# pcb_clk.net
KiCad netlist of a schematic drawn in Altium Designer
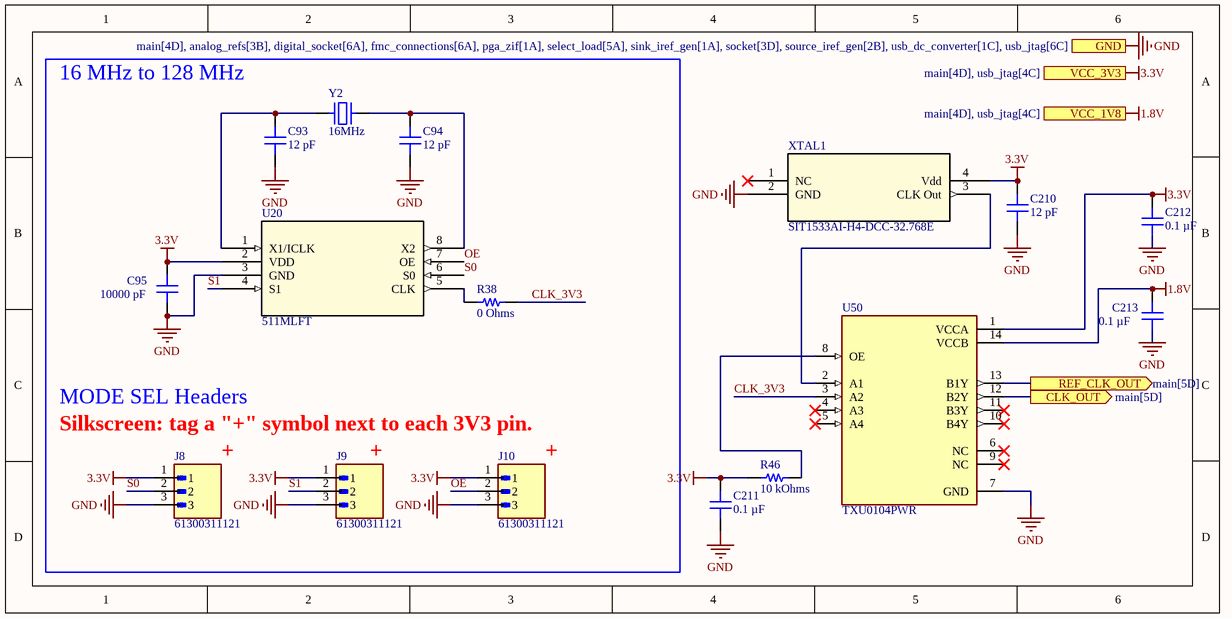
[diagram p0: pcb_clk.SchDoc]

(export (version "E")
  (design (tool "Eeschema 10.0.6"))
  (components
    (comp (ref "C93")
      (value "12 pF")
      (footprint "CAP 0805_2012")
      (description "CAP CER 12PF 250V NP0 0805")
      (fields
        (field (name "PART NUMBER") "251R15S120GV4E")
        (field (name "CAPACITANCE") "12 pF")
        (field (name "MANUFACTURER") "Johanson Technology Inc.")
      )
      (libsource (lib "Celestial Altium Library - altium_library") (part "Capacitor"))
    )
    (comp (ref "C94")
      (value "12 pF")
      (footprint "CAP 0805_2012")
      (description "CAP CER 12PF 250V NP0 0805")
      (fields
        (field (name "PART NUMBER") "251R15S120GV4E")
        (field (name "CAPACITANCE") "12 pF")
        (field (name "MANUFACTURER") "Johanson Technology Inc.")
      )
      (libsource (lib "Celestial Altium Library - altium_library") (part "Capacitor"))
    )
    (comp (ref "C95")
      (value "10000 pF")
      (footprint "CAP 0805_2012")
      (description "CAP CER 0805 10NF 25V C0G 1%")
      (fields
        (field (name "PART NUMBER") "C0805C103F3GEC7800")
        (field (name "CAPACITANCE") "10000 pF")
        (field (name "MANUFACTURER") "KEMET")
      )
      (libsource (lib "Celestial Altium Library - altium_library") (part "Capacitor"))
    )
    (comp (ref "C210")
      (value "12 pF")
      (footprint "CAP 0805_2012")
      (description "CAP CER 12PF 250V NP0 0805")
      (fields
        (field (name "PART NUMBER") "251R15S120GV4E")
        (field (name "CAPACITANCE") "12 pF")
        (field (name "MANUFACTURER") "Johanson Technology Inc.")
      )
      (libsource (lib "Celestial Altium Library - altium_library") (part "Capacitor"))
    )
    (comp (ref "C211")
      (value "0.1 µF")
      (footprint "CAP 0805_2012")
      (description "CAP CER 0.1UF 16V X7R 0805")
      (fields
        (field (name "PART NUMBER") "160R15W104KV4T")
        (field (name "CAPACITANCE") "0.1 µF")
        (field (name "MANUFACTURER") "Johanson Dielectrics Inc.")
      )
      (libsource (lib "Celestial Altium Library - altium_library") (part "Capacitor"))
    )
    (comp (ref "C212")
      (value "0.1 µF")
      (footprint "CAP 0805_2012")
      (description "CAP CER 0.1UF 16V X7R 0805")
      (fields
        (field (name "PART NUMBER") "160R15W104KV4T")
        (field (name "CAPACITANCE") "0.1 µF")
        (field (name "MANUFACTURER") "Johanson Dielectrics Inc.")
      )
      (libsource (lib "Celestial Altium Library - altium_library") (part "Capacitor"))
    )
    (comp (ref "C213")
      (value "0.1 µF")
      (footprint "CAP 0805_2012")
      (description "CAP CER 0.1UF 16V X7R 0805")
      (fields
        (field (name "PART NUMBER") "160R15W104KV4T")
        (field (name "CAPACITANCE") "0.1 µF")
        (field (name "MANUFACTURER") "Johanson Dielectrics Inc.")
      )
      (libsource (lib "Celestial Altium Library - altium_library") (part "Capacitor"))
    )
    (comp (ref "J8")
      (value "61300311121")
      (footprint "WURTH_61300311121")
      (libsource (lib "Connectors") (part "61300311121"))
    )
    (comp (ref "J9")
      (value "61300311121")
      (footprint "WURTH_61300311121")
      (libsource (lib "Connectors") (part "61300311121"))
    )
    (comp (ref "J10")
      (value "61300311121")
      (footprint "WURTH_61300311121")
      (libsource (lib "Connectors") (part "61300311121"))
    )
    (comp (ref "R38")
      (value "0 Ohms")
      (footprint "lagd_pcb:RES 0805_2012")
      (description "RES 0 OHM JUMPER 0805")
      (fields (field (name "PART NUMBER") "560112120002") (field (name "MANUFACTURER") "Würth Elektronik"))
      (libsource (lib "Celestial Altium Library - altium_library") (part "Resistor"))
    )
    (comp (ref "R46")
      (value "10 kOhms")
      (footprint "RES 0805_2012")
      (description "3430 A2 1% 10K 100PPM 1K RL")
      (fields
        (field (name "PART NUMBER") "3430A2F10KTDF")
        (field (name "MANUFACTURER") "TE Connectivity Passive Product")
      )
      (libsource (lib "Celestial Altium Library - altium_library") (part "Resistor"))
    )
    (comp (ref "U20")
      (value "511MLFT")
      (footprint "SOIC8_150MIL_REN")
      (description "No Description Available")
      (libsource (lib "Hemaia") (part "511MLFT"))
    )
    (comp (ref "U50")
      (value "TXU0104PWR")
      (footprint "SOP65P640X120-14N")
      (description "Four channel unidirectional level shifter")
      (fields (field (name "MF") "Texas Instruments"))
      (libsource (lib "TXU0104PWR") (part "TXU0104PWR"))
    )
    (comp (ref "XTAL1")
      (value "SIT1533AI-H4-DCC-32.768E")
      (footprint "XTAL4_SiT1533_SIT")
      (description "Description")
      (fields (field (name "COPYRIGHT") "Copyright (C) 2025 Ultra Librarian. All rights reserved."))
      (libsource (lib "SIT1533AI-H4-DCC-32P768E") (part "SIT1533AI-H4-DCC-32.768E"))
    )
    (comp (ref "Y2")
      (value "16MHz")
      (footprint "TXC 9C")
      (description "CRYSTAL 16.0000MHZ 18PF SMD")
      (fields (field (name "PART NUMBER") "9C-16.000MAAJ-T") (field (name "MANUFACTURER") "TXC CORPORATION"))
      (libsource (lib "Celestial Altium Library - altium_library") (part "TXC Crystal 9C"))
    )
  )
  (nets
    (net (code "1") (name "/CLK_3V3") (class "Default")
      (node (ref "R38") (pin "2") (pinfunction "2_2") (pintype "passive"))
      (node (ref "U50") (pin "3") (pinfunction "A2_3") (pintype "input"))
    )
    (net (code "2") (name "/CLK_OUT") (class "Default")
      (node (ref "U50") (pin "12") (pinfunction "B2Y_12") (pintype "output"))
    )
    (net (code "3") (name "/OE") (class "Default")
      (node (ref "J10") (pin "2") (pinfunction "2_2") (pintype "passive"))
      (node (ref "U20") (pin "7") (pinfunction "OE_7") (pintype "input"))
    )
    (net (code "4") (name "/REF_CLK_OUT") (class "Default")
      (node (ref "U50") (pin "13") (pinfunction "B1Y_13") (pintype "output"))
    )
    (net (code "5") (name "/S0") (class "Default")
      (node (ref "J8") (pin "2") (pinfunction "2_2") (pintype "passive"))
      (node (ref "U20") (pin "6") (pinfunction "S0_6") (pintype "input"))
    )
    (net (code "6") (name "/S1") (class "Default")
      (node (ref "J9") (pin "2") (pinfunction "2_2") (pintype "passive"))
      (node (ref "U20") (pin "4") (pinfunction "S1_4") (pintype "input"))
    )
    (net (code "7") (name "1.8V") (class "Default")
      (node (ref "C213") (pin "2") (pinfunction "2_2") (pintype "passive"))
      (node (ref "U50") (pin "14") (pinfunction "VCCB_14") (pintype "power_in"))
    )
    (net (code "8") (name "3.3V") (class "Default")
      (node (ref "C210") (pin "2") (pinfunction "2_2") (pintype "passive"))
      (node (ref "C211") (pin "2") (pinfunction "2_2") (pintype "passive"))
      (node (ref "C212") (pin "2") (pinfunction "2_2") (pintype "passive"))
      (node (ref "C95") (pin "2") (pinfunction "2_2") (pintype "passive"))
      (node (ref "J10") (pin "1") (pinfunction "1_1") (pintype "passive"))
      (node (ref "J8") (pin "1") (pinfunction "1_1") (pintype "passive"))
      (node (ref "J9") (pin "1") (pinfunction "1_1") (pintype "passive"))
      (node (ref "R46") (pin "1") (pinfunction "1_1") (pintype "passive"))
      (node (ref "U20") (pin "2") (pinfunction "VDD_2") (pintype "power_in"))
      (node (ref "U50") (pin "1") (pinfunction "VCCA_1") (pintype "power_in"))
      (node (ref "XTAL1") (pin "4") (pinfunction "Vdd_4") (pintype "power_in"))
    )
    (net (code "9") (name "GND") (class "Default")
      (node (ref "C210") (pin "1") (pinfunction "1_1") (pintype "passive"))
      (node (ref "C211") (pin "1") (pinfunction "1_1") (pintype "passive"))
      (node (ref "C212") (pin "1") (pinfunction "1_1") (pintype "passive"))
      (node (ref "C213") (pin "1") (pinfunction "1_1") (pintype "passive"))
      (node (ref "C93") (pin "1") (pinfunction "1_1") (pintype "passive"))
      (node (ref "C94") (pin "1") (pinfunction "1_1") (pintype "passive"))
      (node (ref "C95") (pin "1") (pinfunction "1_1") (pintype "passive"))
      (node (ref "J10") (pin "3") (pinfunction "3_3") (pintype "passive"))
      (node (ref "J8") (pin "3") (pinfunction "3_3") (pintype "passive"))
      (node (ref "J9") (pin "3") (pinfunction "3_3") (pintype "passive"))
      (node (ref "U20") (pin "3") (pinfunction "GND_3") (pintype "power_in"))
      (node (ref "U50") (pin "7") (pinfunction "GND_7") (pintype "power_in"))
      (node (ref "XTAL1") (pin "2") (pinfunction "GND_2") (pintype "power_in"))
    )
    (net (code "10") (name "Net-(U20-CLK)") (class "Default")
      (node (ref "R38") (pin "1") (pinfunction "1_1") (pintype "passive"))
      (node (ref "U20") (pin "5") (pinfunction "CLK_5") (pintype "output"))
    )
    (net (code "11") (name "Net-(U20-X1{slash}ICLK)") (class "Default")
      (node (ref "C93") (pin "2") (pinfunction "2_2") (pintype "passive"))
      (node (ref "U20") (pin "1") (pinfunction "X1/ICLK_1") (pintype "input"))
      (node (ref "Y2") (pin "1") (pinfunction "1_1") (pintype "passive"))
    )
    (net (code "12") (name "Net-(U20-X2)") (class "Default")
      (node (ref "C94") (pin "2") (pinfunction "2_2") (pintype "passive"))
      (node (ref "U20") (pin "8") (pinfunction "X2_8") (pintype "output"))
      (node (ref "Y2") (pin "2") (pinfunction "2_2") (pintype "passive"))
    )
    (net (code "13") (name "Net-(U50-A1)") (class "Default")
      (node (ref "U50") (pin "2") (pinfunction "A1_2") (pintype "input"))
      (node (ref "XTAL1") (pin "3") (pinfunction "CLK_Out_3") (pintype "output"))
    )
    (net (code "14") (name "Net-(U50-OE)") (class "Default")
      (node (ref "R46") (pin "2") (pinfunction "2_2") (pintype "passive"))
      (node (ref "U50") (pin "8") (pinfunction "OE_8") (pintype "input"))
    )
    (net (code "15") (name "unconnected-(U50-A3-Pad4)") (class "Default")
      (node (ref "U50") (pin "4") (pinfunction "A3_4") (pintype "input+no_connect"))
    )
    (net (code "16") (name "unconnected-(U50-A4-Pad5)") (class "Default")
      (node (ref "U50") (pin "5") (pinfunction "A4_5") (pintype "input+no_connect"))
    )
    (net (code "17") (name "unconnected-(U50-B3Y-Pad11)") (class "Default")
      (node (ref "U50") (pin "11") (pinfunction "B3Y_11") (pintype "output+no_connect"))
    )
    (net (code "18") (name "unconnected-(U50-B4Y-Pad10)") (class "Default")
      (node (ref "U50") (pin "10") (pinfunction "B4Y_10") (pintype "output+no_connect"))
    )
    (net (code "19") (name "unconnected-(U50-NC-Pad6)") (class "Default")
      (node (ref "U50") (pin "6") (pinfunction "NC_6") (pintype "passive+no_connect"))
    )
    (net (code "20") (name "unconnected-(U50-NC-Pad9)") (class "Default")
      (node (ref "U50") (pin "9") (pinfunction "NC_9") (pintype "passive+no_connect"))
    )
    (net (code "21") (name "unconnected-(XTAL1-NC-Pad1)") (class "Default")
      (node (ref "XTAL1") (pin "1") (pinfunction "NC_1") (pintype "passive+no_connect"))
    )
  )
)
